# badge_0_1.net
KiCad netlist of a schematic drawn in EAGLE
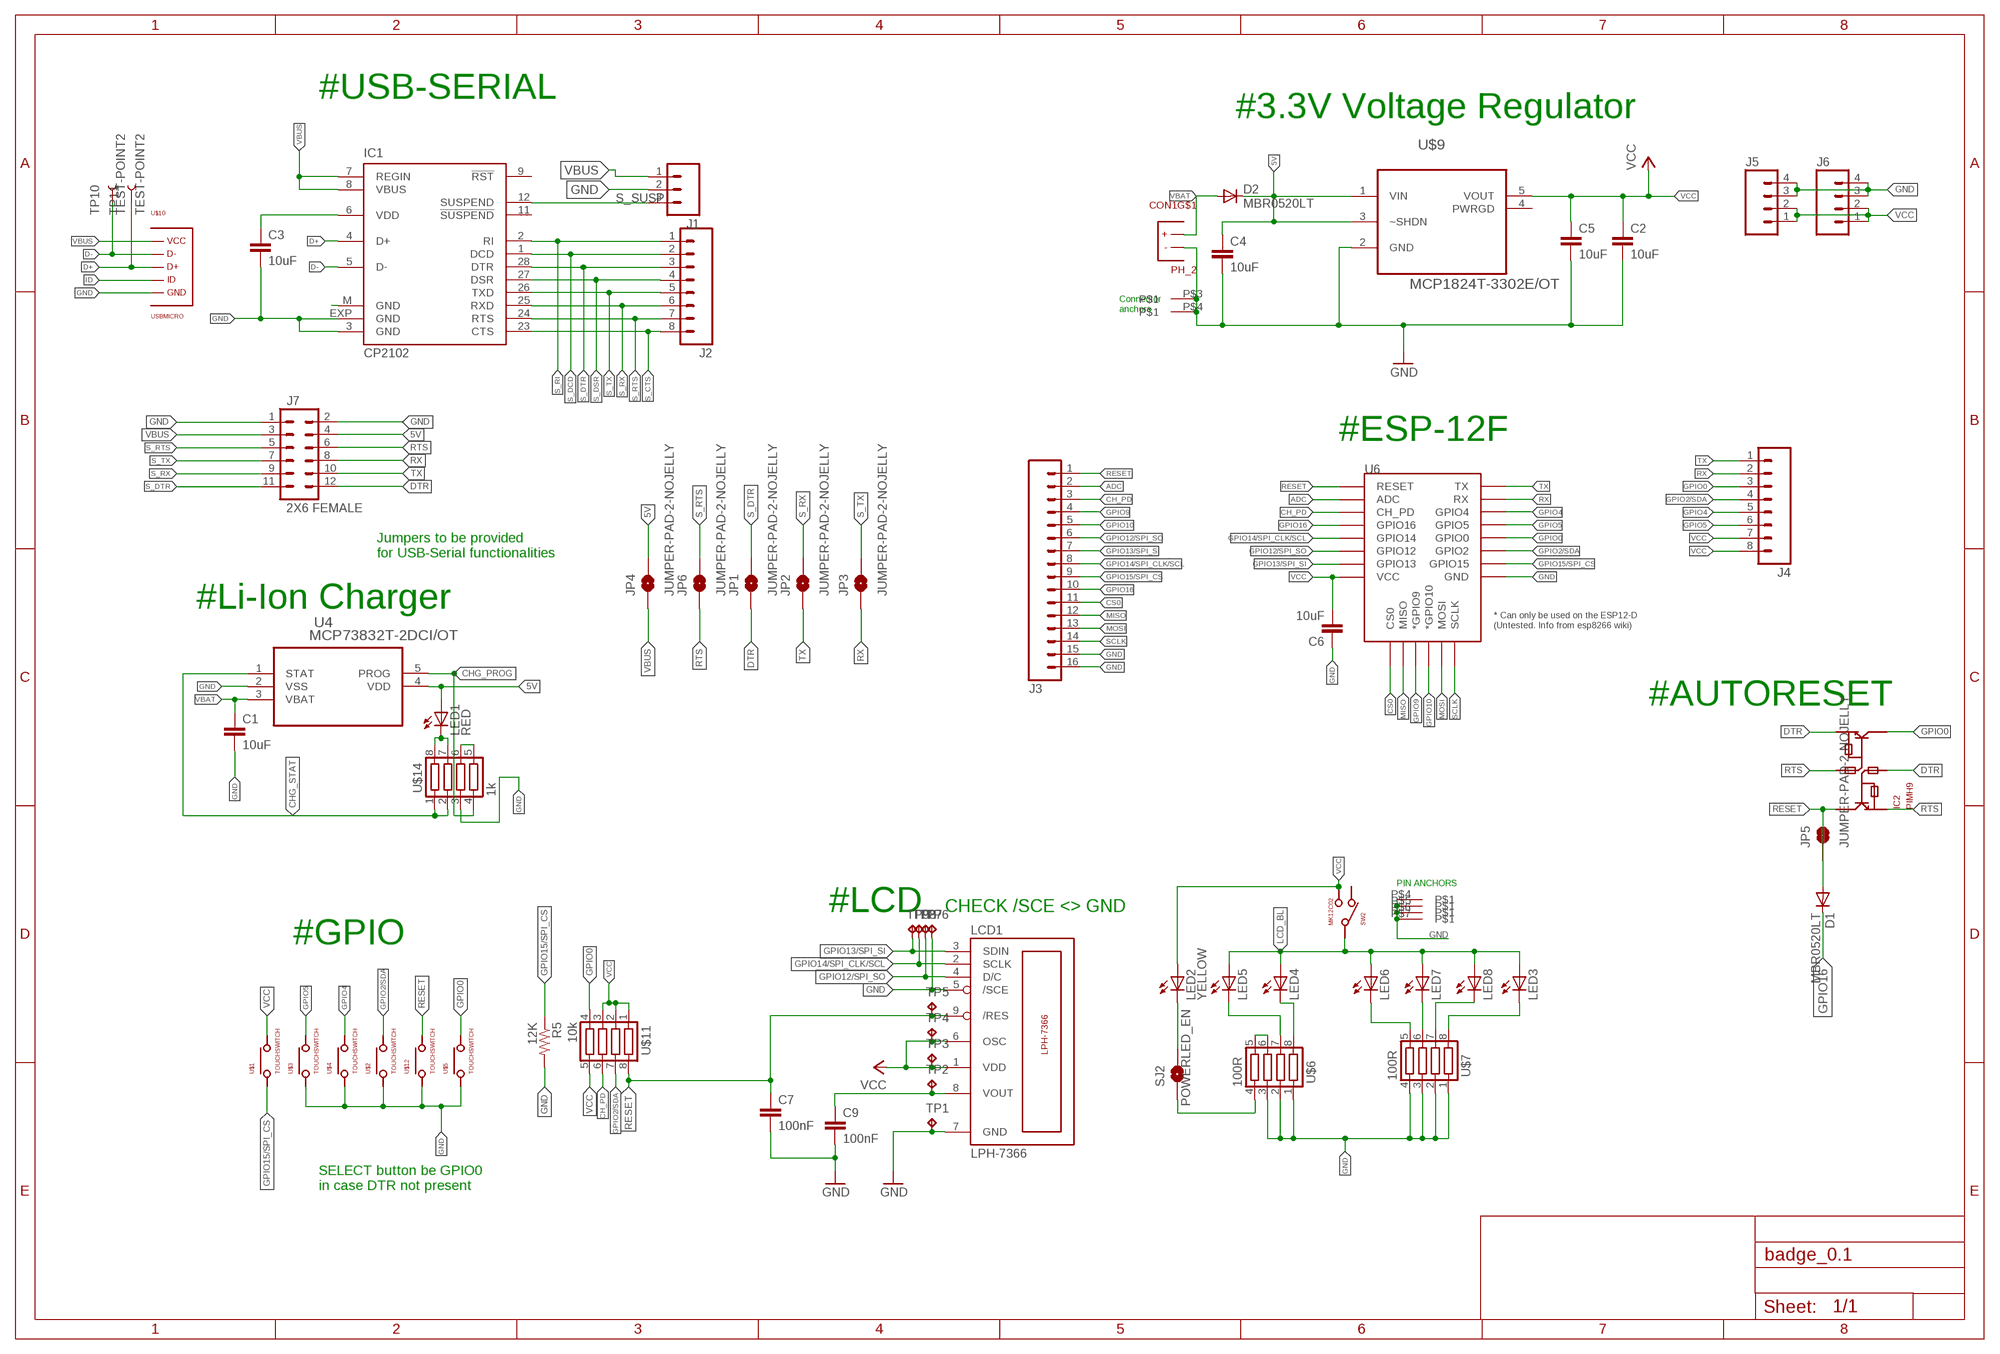
[diagram p0: schematic, sheet 1]

(export (version "E")
  (design (tool "Eeschema 10.0.6"))
  (components
    (comp (ref "C1")
      (value "10uF")
      (footprint "eagle-import:0805-CAP")
      (libsource (lib "eagle-import") (part "1UF-25V-10%(0805){dblquote}"))
    )
    (comp (ref "C2")
      (value "10uF")
      (footprint "eagle-import:0805-CAP")
      (libsource (lib "eagle-import") (part "1UF-25V-10%(0805){dblquote}"))
    )
    (comp (ref "C3")
      (value "10uF")
      (footprint "eagle-import:0805-CAP")
      (libsource (lib "eagle-import") (part "1UF-25V-10%(0805){dblquote}"))
    )
    (comp (ref "C4")
      (value "10uF")
      (footprint "eagle-import:0805-CAP")
      (libsource (lib "eagle-import") (part "1UF-25V-10%(0805){dblquote}"))
    )
    (comp (ref "C5")
      (value "10uF")
      (footprint "eagle-import:0805-CAP")
      (libsource (lib "eagle-import") (part "1UF-25V-10%(0805){dblquote}"))
    )
    (comp (ref "C6")
      (value "10uF")
      (footprint "eagle-import:0805-CAP")
      (libsource (lib "eagle-import") (part "1UF-25V-10%(0805){dblquote}"))
    )
    (comp (ref "C7")
      (value "100nF")
      (footprint "eagle-import:0805-CAP")
      (libsource (lib "eagle-import") (part "1UF-25V-10%(0805){dblquote}"))
    )
    (comp (ref "C9")
      (value "100nF")
      (footprint "eagle-import:0805-CAP")
      (libsource (lib "eagle-import") (part "1UF-25V-10%(0805){dblquote}"))
    )
    (comp (ref "CON1")
      (value "PH_2")
      (footprint "eagle-import:PH_2")
      (libsource (lib "eagle-import") (part "PH_2"))
    )
    (comp (ref "D1")
      (value "MBR0520LT")
      (footprint "eagle-import:SOD123")
      (libsource (lib "eagle-import") (part "MBR0520LT"))
    )
    (comp (ref "D2")
      (value "MBR0520LT")
      (footprint "eagle-import:SOD123")
      (libsource (lib "eagle-import") (part "MBR0520LT"))
    )
    (comp (ref "IC1")
      (value "CP2102")
      (footprint "eagle-import:MLP28")
      (fields (field (name "MF") "FARNELL") (field (name "MPN") "CP2102-GM"))
      (libsource (lib "eagle-import") (part "CP2102"))
    )
    (comp (ref "IC2")
      (value "PIMH9")
      (footprint "eagle-import:SOT457")
      (libsource (lib "eagle-import") (part "PIMH9"))
    )
    (comp (ref "J1")
      (value "M03PTH")
      (footprint "eagle-import:1X03")
      (libsource (lib "eagle-import") (part "M03PTH"))
    )
    (comp (ref "J2")
      (value "M08SILK_FEMALE_PTH")
      (footprint "eagle-import:1X08")
      (libsource (lib "eagle-import") (part "M08SILK_FEMALE_PTH"))
    )
    (comp (ref "J3")
      (value "M16PTH")
      (footprint "eagle-import:1X16")
      (libsource (lib "eagle-import") (part "M16PTH"))
    )
    (comp (ref "J4")
      (value "M08")
      (footprint "eagle-import:1X08_ROUND")
      (libsource (lib "eagle-import") (part "M08"))
    )
    (comp (ref "J5")
      (value "M04PTH")
      (footprint "eagle-import:1X04")
      (libsource (lib "eagle-import") (part "M04PTH"))
    )
    (comp (ref "J6")
      (value "M04PTH")
      (footprint "eagle-import:1X04")
      (libsource (lib "eagle-import") (part "M04PTH"))
    )
    (comp (ref "J7")
      (value "2X6 FEMALE")
      (footprint "eagle-import:2X6")
      (libsource (lib "eagle-import") (part "M06X2PTH_FEMALE"))
    )
    (comp (ref "JP1")
      (value "JUMPER-PAD-2-NOJELLY")
      (footprint "eagle-import:JELLYPAD-JUMPER-2-NO_NO_SILK")
      (libsource (lib "eagle-import") (part "JUMPER-PAD-2-NOJELLY"))
    )
    (comp (ref "JP2")
      (value "JUMPER-PAD-2-NOJELLY")
      (footprint "eagle-import:JELLYPAD-JUMPER-2-NO_NO_SILK")
      (libsource (lib "eagle-import") (part "JUMPER-PAD-2-NOJELLY"))
    )
    (comp (ref "JP3")
      (value "JUMPER-PAD-2-NOJELLY")
      (footprint "eagle-import:JELLYPAD-JUMPER-2-NO_NO_SILK")
      (libsource (lib "eagle-import") (part "JUMPER-PAD-2-NOJELLY"))
    )
    (comp (ref "JP4")
      (value "JUMPER-PAD-2-NOJELLY")
      (footprint "eagle-import:JELLYPAD-JUMPER-2-NO_NO_SILK")
      (libsource (lib "eagle-import") (part "JUMPER-PAD-2-NOJELLY"))
    )
    (comp (ref "JP5")
      (value "JUMPER-PAD-2-NOJELLY")
      (footprint "eagle-import:JELLYPAD-JUMPER-2-NO_NO_SILK")
      (libsource (lib "eagle-import") (part "JUMPER-PAD-2-NOJELLY"))
    )
    (comp (ref "JP6")
      (value "JUMPER-PAD-2-NOJELLY")
      (footprint "eagle-import:JELLYPAD-JUMPER-2-NO_NO_SILK")
      (libsource (lib "eagle-import") (part "JUMPER-PAD-2-NOJELLY"))
    )
    (comp (ref "LCD1")
      (value "LPH-7366")
      (footprint "eagle-import:LPH-7366")
      (libsource (lib "eagle-import") (part "LPH-7366"))
    )
    (comp (ref "LED1")
      (value "RED")
      (footprint "eagle-import:SML0805")
      (libsource (lib "eagle-import") (part "LEDSML0805"))
    )
    (comp (ref "LED2")
      (value "YELLOW")
      (footprint "eagle-import:SML0805")
      (libsource (lib "eagle-import") (part "LEDSML0805"))
    )
    (comp (ref "LED3")
      (value "LEDSML0805")
      (footprint "eagle-import:SML0805")
      (libsource (lib "eagle-import") (part "LEDSML0805"))
    )
    (comp (ref "LED4")
      (value "LEDSML0805")
      (footprint "eagle-import:SML0805")
      (libsource (lib "eagle-import") (part "LEDSML0805"))
    )
    (comp (ref "LED5")
      (value "LEDSML0805")
      (footprint "eagle-import:SML0805")
      (libsource (lib "eagle-import") (part "LEDSML0805"))
    )
    (comp (ref "LED6")
      (value "LEDSML0805")
      (footprint "eagle-import:SML0805")
      (libsource (lib "eagle-import") (part "LEDSML0805"))
    )
    (comp (ref "LED7")
      (value "LEDSML0805")
      (footprint "eagle-import:SML0805")
      (libsource (lib "eagle-import") (part "LEDSML0805"))
    )
    (comp (ref "LED8")
      (value "LEDSML0805")
      (footprint "eagle-import:SML0805")
      (libsource (lib "eagle-import") (part "LEDSML0805"))
    )
    (comp (ref "R5")
      (value "12K")
      (footprint "eagle-import:0805")
      (libsource (lib "eagle-import") (part "RESISTOR0805-RES"))
    )
    (comp (ref "SJ2")
      (value "POWERLED_EN")
      (footprint "eagle-import:SJ_2S-TRACE")
      (libsource (lib "eagle-import") (part "SOLDERJUMPERTRACE"))
    )
    (comp (ref "SW2")
      (value "MK12C02")
      (footprint "eagle-import:MK12C02")
      (libsource (lib "eagle-import") (part "MK12C02"))
    )
    (comp (ref "TP1")
      (value "TPB1,27")
      (footprint "eagle-import:B1,27")
      (libsource (lib "eagle-import") (part "TPB1,27"))
    )
    (comp (ref "TP2")
      (value "TPB1,27")
      (footprint "eagle-import:B1,27")
      (libsource (lib "eagle-import") (part "TPB1,27"))
    )
    (comp (ref "TP3")
      (value "TPB1,27")
      (footprint "eagle-import:B1,27")
      (libsource (lib "eagle-import") (part "TPB1,27"))
    )
    (comp (ref "TP4")
      (value "TPB1,27")
      (footprint "eagle-import:B1,27")
      (libsource (lib "eagle-import") (part "TPB1,27"))
    )
    (comp (ref "TP5")
      (value "TPB1,27")
      (footprint "eagle-import:B1,27")
      (libsource (lib "eagle-import") (part "TPB1,27"))
    )
    (comp (ref "TP6")
      (value "TPB1,27")
      (footprint "eagle-import:B1,27")
      (libsource (lib "eagle-import") (part "TPB1,27"))
    )
    (comp (ref "TP7")
      (value "TPB1,27")
      (footprint "eagle-import:B1,27")
      (libsource (lib "eagle-import") (part "TPB1,27"))
    )
    (comp (ref "TP8")
      (value "TPB1,27")
      (footprint "eagle-import:B1,27")
      (libsource (lib "eagle-import") (part "TPB1,27"))
    )
    (comp (ref "TP9")
      (value "TPB1,27")
      (footprint "eagle-import:B1,27")
      (libsource (lib "eagle-import") (part "TPB1,27"))
    )
    (comp (ref "TP10")
      (value "TEST-POINT2")
      (footprint "eagle-import:PAD.02X.02")
      (libsource (lib "eagle-import") (part "TEST-POINT2"))
    )
    (comp (ref "TP11")
      (value "TEST-POINT2")
      (footprint "eagle-import:PAD.02X.02")
      (libsource (lib "eagle-import") (part "TEST-POINT2"))
    )
    (comp (ref "U$1")
      (value "TOUCHSWITCH")
      (footprint "eagle-import:EVQQWN03W")
      (libsource (lib "eagle-import") (part "TOUCHSWITCH"))
    )
    (comp (ref "U$2")
      (value "TOUCHSWITCH")
      (footprint "eagle-import:EVQQWN03W")
      (libsource (lib "eagle-import") (part "TOUCHSWITCH"))
    )
    (comp (ref "U$3")
      (value "TOUCHSWITCH")
      (footprint "eagle-import:EVQQWN03W")
      (libsource (lib "eagle-import") (part "TOUCHSWITCH"))
    )
    (comp (ref "U$4")
      (value "TOUCHSWITCH")
      (footprint "eagle-import:EVQQWN03W")
      (libsource (lib "eagle-import") (part "TOUCHSWITCH"))
    )
    (comp (ref "U$5")
      (value "TOUCHSWITCH")
      (footprint "eagle-import:EVQQWN03W")
      (libsource (lib "eagle-import") (part "TOUCHSWITCH"))
    )
    (comp (ref "U$6")
      (value "100R")
      (footprint "eagle-import:YC164")
      (libsource (lib "eagle-import") (part "RES_ARR"))
    )
    (comp (ref "U$7")
      (value "100R")
      (footprint "eagle-import:YC164")
      (libsource (lib "eagle-import") (part "RES_ARR"))
    )
    (comp (ref "U$9")
      (value "MCP1824T-3302E/OT")
      (footprint "eagle-import:SOT95P270X145-5N")
      (libsource (lib "eagle-import") (part "MCP1824T-3302E/OT"))
    )
    (comp (ref "U$10")
      (value "USBMICRO")
      (footprint "eagle-import:USBMICRO")
      (libsource (lib "eagle-import") (part "USBMICRO"))
    )
    (comp (ref "U$11")
      (value "10k")
      (footprint "eagle-import:YC164")
      (libsource (lib "eagle-import") (part "RES_ARR"))
    )
    (comp (ref "U$12")
      (value "TOUCHSWITCH")
      (footprint "eagle-import:EVQQWN03W")
      (libsource (lib "eagle-import") (part "TOUCHSWITCH"))
    )
    (comp (ref "U$14")
      (value "1k")
      (footprint "eagle-import:YC164")
      (libsource (lib "eagle-import") (part "RES_ARR"))
    )
    (comp (ref "U4")
      (value "MCP73832T-2DCI/OT")
      (footprint "eagle-import:SOT95P300X145-5N")
      (libsource (lib "eagle-import") (part "MCP73832T-2DCI/OT"))
    )
    (comp (ref "U6")
      (value "ESP12ESMD")
      (footprint "eagle-import:ESP12E-SMD")
      (libsource (lib "eagle-import") (part "ESP12ESMD"))
    )
  )
  (nets
    (net (code "1") (name "/S_SUSP") (class "Default")
      (node (ref "IC1") (pin "12") (pinfunction "SUSPEND_12") (pintype "output"))
      (node (ref "J1") (pin "3") (pinfunction "3_3") (pintype "passive"))
    )
    (net (code "2") (name "5V") (class "Default")
      (node (ref "C4") (pin "1") (pinfunction "1_1") (pintype "passive"))
      (node (ref "D2") (pin "C") (pinfunction "C_C") (pintype "passive"))
      (node (ref "J7") (pin "4") (pinfunction "4_4") (pintype "passive"))
      (node (ref "JP4") (pin "2") (pinfunction "2_2") (pintype "passive"))
      (node (ref "LED1") (pin "A") (pinfunction "A_A") (pintype "passive"))
      (node (ref "U$9") (pin "1") (pinfunction "VIN_1") (pintype "input"))
      (node (ref "U$9") (pin "3") (pinfunction "~{SHDN}_3") (pintype "input"))
      (node (ref "U4") (pin "4") (pinfunction "VDD_4") (pintype "power_in"))
    )
    (net (code "3") (name "ADC") (class "Default")
      (node (ref "J3") (pin "2") (pinfunction "2_2") (pintype "passive"))
      (node (ref "U6") (pin "ADC") (pinfunction "ADC_ADC") (pintype "bidirectional"))
    )
    (net (code "4") (name "CHG_PROG") (class "Default")
      (node (ref "U$14") (pin "4") (pinfunction "4_4") (pintype "passive"))
      (node (ref "U4") (pin "5") (pinfunction "PROG_5") (pintype "input"))
    )
    (net (code "5") (name "CHG_STAT") (class "Default")
      (node (ref "U$14") (pin "1") (pinfunction "1_1") (pintype "passive"))
      (node (ref "U$14") (pin "2") (pinfunction "2_2") (pintype "passive"))
      (node (ref "U4") (pin "1") (pinfunction "STAT_1") (pintype "input"))
    )
    (net (code "6") (name "CH_PD") (class "Default")
      (node (ref "J3") (pin "3") (pinfunction "3_3") (pintype "passive"))
      (node (ref "U$11") (pin "6") (pinfunction "6_6") (pintype "passive"))
      (node (ref "U6") (pin "CH_PD") (pinfunction "CH_PD_CH_PD") (pintype "bidirectional"))
    )
    (net (code "7") (name "CS0") (class "Default")
      (node (ref "J3") (pin "11") (pinfunction "11_11") (pintype "passive"))
      (node (ref "U6") (pin "CS0") (pinfunction "CS0_CS0") (pintype "bidirectional"))
    )
    (net (code "8") (name "D+") (class "Default")
      (node (ref "IC1") (pin "4") (pinfunction "D+_4") (pintype "bidirectional"))
      (node (ref "TP11") (pin "P$1") (pinfunction "1_P$1") (pintype "bidirectional"))
      (node (ref "U$10") (pin "P$D+") (pinfunction "P$D+_P$D+") (pintype "bidirectional"))
    )
    (net (code "9") (name "D-") (class "Default")
      (node (ref "IC1") (pin "5") (pinfunction "D-_5") (pintype "bidirectional"))
      (node (ref "TP10") (pin "P$1") (pinfunction "1_P$1") (pintype "bidirectional"))
      (node (ref "U$10") (pin "P$D-") (pinfunction "P$D-_P$D-") (pintype "bidirectional"))
    )
    (net (code "10") (name "DTR") (class "Default")
      (node (ref "IC2") (pin "P$2") (pinfunction "P$2_P$2") (pintype "bidirectional"))
      (node (ref "IC2") (pin "P$4") (pinfunction "P$4_P$4") (pintype "bidirectional"))
      (node (ref "J7") (pin "12") (pinfunction "12_12") (pintype "passive"))
      (node (ref "JP1") (pin "1") (pinfunction "1_1") (pintype "passive"))
    )
    (net (code "11") (name "GND") (class "Default")
      (node (ref "C1") (pin "2") (pinfunction "2_2") (pintype "passive"))
      (node (ref "C2") (pin "2") (pinfunction "2_2") (pintype "passive"))
      (node (ref "C3") (pin "2") (pinfunction "2_2") (pintype "passive"))
      (node (ref "C4") (pin "2") (pinfunction "2_2") (pintype "passive"))
      (node (ref "C5") (pin "2") (pinfunction "2_2") (pintype "passive"))
      (node (ref "C6") (pin "1") (pinfunction "1_1") (pintype "passive"))
      (node (ref "C7") (pin "2") (pinfunction "2_2") (pintype "passive"))
      (node (ref "C9") (pin "2") (pinfunction "2_2") (pintype "passive"))
      (node (ref "CON1") (pin "P$1") (pinfunction "P$2_P$1") (pintype "bidirectional"))
      (node (ref "CON1") (pin "P$3") (pinfunction "P$1_P$3") (pintype "bidirectional"))
      (node (ref "CON1") (pin "P$4") (pinfunction "P$1_P$4") (pintype "bidirectional"))
      (node (ref "IC1") (pin "3") (pinfunction "GND_3") (pintype "power_in"))
      (node (ref "IC1") (pin "EXP") (pinfunction "GND_EXP") (pintype "power_in"))
      (node (ref "J1") (pin "2") (pinfunction "2_2") (pintype "passive"))
      (node (ref "J3") (pin "15") (pinfunction "15_15") (pintype "passive"))
      (node (ref "J3") (pin "16") (pinfunction "16_16") (pintype "passive"))
      (node (ref "J5") (pin "3") (pinfunction "3_3") (pintype "passive"))
      (node (ref "J5") (pin "4") (pinfunction "4_4") (pintype "passive"))
      (node (ref "J6") (pin "3") (pinfunction "3_3") (pintype "passive"))
      (node (ref "J6") (pin "4") (pinfunction "4_4") (pintype "passive"))
      (node (ref "J7") (pin "1") (pinfunction "1_1") (pintype "passive"))
      (node (ref "J7") (pin "2") (pinfunction "2_2") (pintype "passive"))
      (node (ref "LCD1") (pin "5") (pinfunction "/SCE_5") (pintype "input"))
      (node (ref "LCD1") (pin "7") (pinfunction "GND_7") (pintype "power_in"))
      (node (ref "R5") (pin "2") (pinfunction "2_2") (pintype "passive"))
      (node (ref "SW2") (pin "P$4") (pinfunction "P$1_P$4") (pintype "bidirectional"))
      (node (ref "SW2") (pin "P$5") (pinfunction "P$1_P$5") (pintype "bidirectional"))
      (node (ref "SW2") (pin "P$6") (pinfunction "P$1_P$6") (pintype "bidirectional"))
      (node (ref "SW2") (pin "P$7") (pinfunction "P$1_P$7") (pintype "bidirectional"))
      (node (ref "TP1") (pin "TP") (pinfunction "TP_TP") (pintype "input"))
      (node (ref "TP6") (pin "TP") (pinfunction "TP_TP") (pintype "input"))
      (node (ref "U$10") (pin "P$GND") (pinfunction "P$GND_P$GND") (pintype "bidirectional"))
      (node (ref "U$12") (pin "P$1") (pinfunction "P$1_P$1") (pintype "bidirectional"))
      (node (ref "U$12") (pin "P$4") (pinfunction "P$1_P$4") (pintype "bidirectional"))
      (node (ref "U$14") (pin "3") (pinfunction "3_3") (pintype "passive"))
      (node (ref "U$2") (pin "P$1") (pinfunction "P$1_P$1") (pintype "bidirectional"))
      (node (ref "U$2") (pin "P$4") (pinfunction "P$1_P$4") (pintype "bidirectional"))
      (node (ref "U$3") (pin "P$1") (pinfunction "P$1_P$1") (pintype "bidirectional"))
      (node (ref "U$3") (pin "P$4") (pinfunction "P$1_P$4") (pintype "bidirectional"))
      (node (ref "U$4") (pin "P$1") (pinfunction "P$1_P$1") (pintype "bidirectional"))
      (node (ref "U$4") (pin "P$4") (pinfunction "P$1_P$4") (pintype "bidirectional"))
      (node (ref "U$5") (pin "P$1") (pinfunction "P$1_P$1") (pintype "bidirectional"))
      (node (ref "U$5") (pin "P$4") (pinfunction "P$1_P$4") (pintype "bidirectional"))
      (node (ref "U$6") (pin "1") (pinfunction "1_1") (pintype "passive"))
      (node (ref "U$6") (pin "2") (pinfunction "2_2") (pintype "passive"))
      (node (ref "U$6") (pin "3") (pinfunction "3_3") (pintype "passive"))
      (node (ref "U$7") (pin "1") (pinfunction "1_1") (pintype "passive"))
      (node (ref "U$7") (pin "2") (pinfunction "2_2") (pintype "passive"))
      (node (ref "U$7") (pin "3") (pinfunction "3_3") (pintype "passive"))
      (node (ref "U$7") (pin "4") (pinfunction "4_4") (pintype "passive"))
      (node (ref "U$9") (pin "2") (pinfunction "GND_2") (pintype "passive"))
      (node (ref "U4") (pin "2") (pinfunction "VSS_2") (pintype "passive"))
      (node (ref "U6") (pin "GND") (pinfunction "GND_GND") (pintype "bidirectional"))
    )
    (net (code "12") (name "GPIO0") (class "Default")
      (node (ref "IC2") (pin "P$3") (pinfunction "P$3_P$3") (pintype "bidirectional"))
      (node (ref "J4") (pin "3") (pinfunction "3_3") (pintype "passive"))
      (node (ref "U$11") (pin "4") (pinfunction "4_4") (pintype "passive"))
      (node (ref "U$5") (pin "P$2") (pinfunction "P$2_P$2") (pintype "bidirectional"))
      (node (ref "U$5") (pin "P$3") (pinfunction "P$2_P$3") (pintype "bidirectional"))
      (node (ref "U6") (pin "GPIO0") (pinfunction "GPIO0_GPIO0") (pintype "bidirectional"))
    )
    (net (code "13") (name "GPIO2{slash}SDA") (class "Default")
      (node (ref "J4") (pin "4") (pinfunction "4_4") (pintype "passive"))
      (node (ref "U$11") (pin "7") (pinfunction "7_7") (pintype "passive"))
      (node (ref "U$2") (pin "P$2") (pinfunction "P$2_P$2") (pintype "bidirectional"))
      (node (ref "U$2") (pin "P$3") (pinfunction "P$2_P$3") (pintype "bidirectional"))
      (node (ref "U6") (pin "GPIO2") (pinfunction "GPIO2_GPIO2") (pintype "bidirectional"))
    )
    (net (code "14") (name "GPIO4") (class "Default")
      (node (ref "J4") (pin "5") (pinfunction "5_5") (pintype "passive"))
      (node (ref "U$4") (pin "P$2") (pinfunction "P$2_P$2") (pintype "bidirectional"))
      (node (ref "U$4") (pin "P$3") (pinfunction "P$2_P$3") (pintype "bidirectional"))
      (node (ref "U6") (pin "GPIO4") (pinfunction "GPIO4_GPIO4") (pintype "bidirectional"))
    )
    (net (code "15") (name "GPIO5") (class "Default")
      (node (ref "J4") (pin "6") (pinfunction "6_6") (pintype "passive"))
      (node (ref "U$3") (pin "P$2") (pinfunction "P$2_P$2") (pintype "bidirectional"))
      (node (ref "U$3") (pin "P$3") (pinfunction "P$2_P$3") (pintype "bidirectional"))
      (node (ref "U6") (pin "GPIO5") (pinfunction "GPIO5_GPIO5") (pintype "bidirectional"))
    )
    (net (code "16") (name "GPIO9") (class "Default")
      (node (ref "J3") (pin "4") (pinfunction "4_4") (pintype "passive"))
      (node (ref "U6") (pin "GPIO9") (pinfunction "*GPIO9_GPIO9") (pintype "bidirectional"))
    )
    (net (code "17") (name "GPIO10") (class "Default")
      (node (ref "J3") (pin "5") (pinfunction "5_5") (pintype "passive"))
      (node (ref "U6") (pin "GPIO10") (pinfunction "*GPIO10_GPIO10") (pintype "bidirectional"))
    )
    (net (code "18") (name "GPIO12{slash}SPI_SO") (class "Default")
      (node (ref "J3") (pin "6") (pinfunction "6_6") (pintype "passive"))
      (node (ref "LCD1") (pin "4") (pinfunction "D/C_4") (pintype "input"))
      (node (ref "TP7") (pin "TP") (pinfunction "TP_TP") (pintype "input"))
      (node (ref "U6") (pin "GPIO12") (pinfunction "GPIO12_GPIO12") (pintype "bidirectional"))
    )
    (net (code "19") (name "GPIO13{slash}SPI_SI") (class "Default")
      (node (ref "J3") (pin "7") (pinfunction "7_7") (pintype "passive"))
      (node (ref "LCD1") (pin "3") (pinfunction "SDIN_3") (pintype "input"))
      (node (ref "TP9") (pin "TP") (pinfunction "TP_TP") (pintype "input"))
      (node (ref "U6") (pin "GPIO13") (pinfunction "GPIO13_GPIO13") (pintype "bidirectional"))
    )
    (net (code "20") (name "GPIO14{slash}SPI_CLK{slash}SCL") (class "Default")
      (node (ref "J3") (pin "8") (pinfunction "8_8") (pintype "passive"))
      (node (ref "LCD1") (pin "2") (pinfunction "SCLK_2") (pintype "input"))
      (node (ref "TP8") (pin "TP") (pinfunction "TP_TP") (pintype "input"))
      (node (ref "U6") (pin "GPIO14") (pinfunction "GPIO14_GPIO14") (pintype "bidirectional"))
    )
    (net (code "21") (name "GPIO15{slash}SPI_CS") (class "Default")
      (node (ref "J3") (pin "9") (pinfunction "9_9") (pintype "passive"))
      (node (ref "R5") (pin "1") (pinfunction "1_1") (pintype "passive"))
      (node (ref "U$1") (pin "P$1") (pinfunction "P$1_P$1") (pintype "bidirectional"))
      (node (ref "U$1") (pin "P$4") (pinfunction "P$1_P$4") (pintype "bidirectional"))
      (node (ref "U6") (pin "GPIO15") (pinfunction "GPIO15_GPIO15") (pintype "bidirectional"))
    )
    (net (code "22") (name "GPIO16") (class "Default")
      (node (ref "D1") (pin "C") (pinfunction "C_C") (pintype "passive"))
      (node (ref "J3") (pin "10") (pinfunction "10_10") (pintype "passive"))
      (node (ref "U6") (pin "GPIO16") (pinfunction "GPIO16_GPIO16") (pintype "bidirectional"))
    )
    (net (code "23") (name "ID") (class "Default")
      (node (ref "U$10") (pin "P$ID") (pinfunction "P$ID_P$ID") (pintype "bidirectional"))
    )
    (net (code "24") (name "LCD_BL") (class "Default")
      (node (ref "LED3") (pin "A") (pinfunction "A_A") (pintype "passive"))
      (node (ref "LED4") (pin "A") (pinfunction "A_A") (pintype "passive"))
      (node (ref "LED5") (pin "A") (pinfunction "A_A") (pintype "passive"))
      (node (ref "LED6") (pin "A") (pinfunction "A_A") (pintype "passive"))
      (node (ref "LED7") (pin "A") (pinfunction "A_A") (pintype "passive"))
      (node (ref "LED8") (pin "A") (pinfunction "A_A") (pintype "passive"))
      (node (ref "SW2") (pin "P$2") (pinfunction "P$1_P$2") (pintype "bidirectional"))
    )
    (net (code "25") (name "MISO") (class "Default")
      (node (ref "J3") (pin "12") (pinfunction "12_12") (pintype "passive"))
      (node (ref "U6") (pin "MISO") (pinfunction "MISO_MISO") (pintype "bidirectional"))
    )
    (net (code "26") (name "MOSI") (class "Default")
      (node (ref "J3") (pin "13") (pinfunction "13_13") (pintype "passive"))
      (node (ref "U6") (pin "MOSI") (pinfunction "MOSI_MOSI") (pintype "bidirectional"))
    )
    (net (code "27") (name "Net-(IC1-VDD)") (class "Default")
      (node (ref "C3") (pin "1") (pinfunction "1_1") (pintype "passive"))
      (node (ref "IC1") (pin "6") (pinfunction "VDD_6") (pintype "power_in"))
    )
    (net (code "28") (name "Net-(LCD1-VOUT)") (class "Default")
      (node (ref "C9") (pin "1") (pinfunction "1_1") (pintype "passive"))
      (node (ref "LCD1") (pin "8") (pinfunction "VOUT_8") (pintype "passive"))
      (node (ref "TP2") (pin "TP") (pinfunction "TP_TP") (pintype "input"))
    )
    (net (code "29") (name "Net-(LED1-PadC)") (class "Default")
      (node (ref "LED1") (pin "C") (pinfunction "C_C") (pintype "passive"))
      (node (ref "U$14") (pin "7") (pinfunction "7_7") (pintype "passive"))
      (node (ref "U$14") (pin "8") (pinfunction "8_8") (pintype "passive"))
    )
    (net (code "30") (name "Net-(LED2-PadC)") (class "Default")
      (node (ref "LED2") (pin "C") (pinfunction "C_C") (pintype "passive"))
      (node (ref "SJ2") (pin "2") (pinfunction "2_2") (pintype "passive"))
    )
    (net (code "31") (name "Net-(LED3-PadC)") (class "Default")
      (node (ref "LED3") (pin "C") (pinfunction "C_C") (pintype "passive"))
      (node (ref "U$7") (pin "8") (pinfunction "8_8") (pintype "passive"))
    )
    (net (code "32") (name "Net-(LED4-PadC)") (class "Default")
      (node (ref "LED4") (pin "C") (pinfunction "C_C") (pintype "passive"))
      (node (ref "U$6") (pin "8") (pinfunction "8_8") (pintype "passive"))
    )
    (net (code "33") (name "Net-(LED5-PadC)") (class "Default")
      (node (ref "LED5") (pin "C") (pinfunction "C_C") (pintype "passive"))
      (node (ref "U$6") (pin "7") (pinfunction "7_7") (pintype "passive"))
    )
    (net (code "34") (name "Net-(LED6-PadC)") (class "Default")
      (node (ref "LED6") (pin "C") (pinfunction "C_C") (pintype "passive"))
      (node (ref "U$7") (pin "5") (pinfunction "5_5") (pintype "passive"))
    )
    (net (code "35") (name "Net-(LED7-PadC)") (class "Default")
      (node (ref "LED7") (pin "C") (pinfunction "C_C") (pintype "passive"))
      (node (ref "U$7") (pin "6") (pinfunction "6_6") (pintype "passive"))
    )
    (net (code "36") (name "Net-(LED8-PadC)") (class "Default")
      (node (ref "LED8") (pin "C") (pinfunction "C_C") (pintype "passive"))
      (node (ref "U$7") (pin "7") (pinfunction "7_7") (pintype "passive"))
    )
    (net (code "37") (name "Net-(SJ2-Pad1)") (class "Default")
      (node (ref "SJ2") (pin "1") (pinfunction "1_1") (pintype "passive"))
      (node (ref "U$6") (pin "4") (pinfunction "4_4") (pintype "passive"))
    )
    (net (code "38") (name "Net-(U$6-Pad5)") (class "Default")
      (node (ref "U$6") (pin "5") (pinfunction "5_5") (pintype "passive"))
      (node (ref "U$6") (pin "6") (pinfunction "6_6") (pintype "passive"))
    )
    (net (code "39") (name "Net-(U$14-Pad5)") (class "Default")
      (node (ref "U$14") (pin "5") (pinfunction "5_5") (pintype "passive"))
      (node (ref "U$14") (pin "6") (pinfunction "6_6") (pintype "passive"))
    )
    (net (code "40") (name "RESET") (class "Default")
      (node (ref "C7") (pin "1") (pinfunction "1_1") (pintype "passive"))
      (node (ref "D1") (pin "A") (pinfunction "A_A") (pintype "passive"))
      (node (ref "IC2") (pin "P$6") (pinfunction "P$6_P$6") (pintype "bidirectional"))
      (node (ref "J3") (pin "1") (pinfunction "1_1") (pintype "passive"))
      (node (ref "JP5") (pin "1") (pinfunction "1_1") (pintype "passive"))
      (node (ref "JP5") (pin "2") (pinfunction "2_2") (pintype "passive"))
      (node (ref "LCD1") (pin "9") (pinfunction "/RES_9") (pintype "input"))
      (node (ref "TP5") (pin "TP") (pinfunction "TP_TP") (pintype "input"))
      (node (ref "U$11") (pin "8") (pinfunction "8_8") (pintype "passive"))
      (node (ref "U$12") (pin "P$2") (pinfunction "P$2_P$2") (pintype "bidirectional"))
      (node (ref "U$12") (pin "P$3") (pinfunction "P$2_P$3") (pintype "bidirectional"))
      (node (ref "U6") (pin "RESET") (pinfunction "RESET_RESET") (pintype "bidirectional"))
    )
    (net (code "41") (name "RTS") (class "Default")
      (node (ref "IC2") (pin "P$1") (pinfunction "P$1_P$1") (pintype "bidirectional"))
      (node (ref "IC2") (pin "P$5") (pinfunction "P$5_P$5") (pintype "bidirectional"))
      (node (ref "J7") (pin "6") (pinfunction "6_6") (pintype "passive"))
      (node (ref "JP6") (pin "1") (pinfunction "1_1") (pintype "passive"))
    )
    (net (code "42") (name "RX") (class "Default")
      (node (ref "J4") (pin "2") (pinfunction "2_2") (pintype "passive"))
      (node (ref "J7") (pin "8") (pinfunction "8_8") (pintype "passive"))
      (node (ref "JP3") (pin "1") (pinfunction "1_1") (pintype "passive"))
      (node (ref "U6") (pin "RXD0") (pinfunction "RX_RXD0") (pintype "bidirectional"))
    )
    (net (code "43") (name "SCLK") (class "Default")
      (node (ref "J3") (pin "14") (pinfunction "14_14") (pintype "passive"))
      (node (ref "U6") (pin "SCLK") (pinfunction "SCLK_SCLK") (pintype "bidirectional"))
    )
    (net (code "44") (name "S_CTS") (class "Default")
      (node (ref "IC1") (pin "23") (pinfunction "CTS_23") (pintype "input"))
      (node (ref "J2") (pin "8") (pinfunction "8_8") (pintype "passive"))
    )
    (net (code "45") (name "S_DCD") (class "Default")
      (node (ref "IC1") (pin "1") (pinfunction "DCD_1") (pintype "input"))
      (node (ref "J2") (pin "2") (pinfunction "2_2") (pintype "passive"))
    )
    (net (code "46") (name "S_DSR") (class "Default")
      (node (ref "IC1") (pin "27") (pinfunction "DSR_27") (pintype "input"))
      (node (ref "J2") (pin "4") (pinfunction "4_4") (pintype "passive"))
    )
    (net (code "47") (name "S_DTR") (class "Default")
      (node (ref "IC1") (pin "28") (pinfunction "DTR_28") (pintype "output"))
      (node (ref "J2") (pin "3") (pinfunction "3_3") (pintype "passive"))
      (node (ref "J7") (pin "11") (pinfunction "11_11") (pintype "passive"))
      (node (ref "JP1") (pin "2") (pinfunction "2_2") (pintype "passive"))
    )
    (net (code "48") (name "S_RI") (class "Default")
      (node (ref "IC1") (pin "2") (pinfunction "RI_2") (pintype "input"))
      (node (ref "J2") (pin "1") (pinfunction "1_1") (pintype "passive"))
    )
    (net (code "49") (name "S_RTS") (class "Default")
      (node (ref "IC1") (pin "24") (pinfunction "RTS_24") (pintype "output"))
      (node (ref "J2") (pin "7") (pinfunction "7_7") (pintype "passive"))
      (node (ref "J7") (pin "5") (pinfunction "5_5") (pintype "passive"))
      (node (ref "JP6") (pin "2") (pinfunction "2_2") (pintype "passive"))
    )
    (net (code "50") (name "S_RX") (class "Default")
      (node (ref "IC1") (pin "25") (pinfunction "RXD_25") (pintype "input"))
      (node (ref "J2") (pin "6") (pinfunction "6_6") (pintype "passive"))
      (node (ref "J7") (pin "9") (pinfunction "9_9") (pintype "passive"))
      (node (ref "JP2") (pin "2") (pinfunction "2_2") (pintype "passive"))
    )
    (net (code "51") (name "S_TX") (class "Default")
      (node (ref "IC1") (pin "26") (pinfunction "TXD_26") (pintype "output"))
      (node (ref "J2") (pin "5") (pinfunction "5_5") (pintype "passive"))
      (node (ref "J7") (pin "7") (pinfunction "7_7") (pintype "passive"))
      (node (ref "JP3") (pin "2") (pinfunction "2_2") (pintype "passive"))
    )
    (net (code "52") (name "TX") (class "Default")
      (node (ref "J4") (pin "1") (pinfunction "1_1") (pintype "passive"))
      (node (ref "J7") (pin "10") (pinfunction "10_10") (pintype "passive"))
      (node (ref "JP2") (pin "1") (pinfunction "1_1") (pintype "passive"))
      (node (ref "U6") (pin "TXD0") (pinfunction "TX_TXD0") (pintype "bidirectional"))
    )
    (net (code "53") (name "VBAT") (class "Default")
      (node (ref "C1") (pin "1") (pinfunction "1_1") (pintype "passive"))
      (node (ref "CON1") (pin "P$2") (pinfunction "P$1_P$2") (pintype "bidirectional"))
      (node (ref "D2") (pin "A") (pinfunction "A_A") (pintype "passive"))
      (node (ref "U4") (pin "3") (pinfunction "VBAT_3") (pintype "input"))
    )
    (net (code "54") (name "VBUS") (class "Default")
      (node (ref "IC1") (pin "7") (pinfunction "REGIN_7") (pintype "passive"))
      (node (ref "IC1") (pin "8") (pinfunction "VBUS_8") (pintype "input"))
      (node (ref "J1") (pin "1") (pinfunction "1_1") (pintype "passive"))
      (node (ref "J7") (pin "3") (pinfunction "3_3") (pintype "passive"))
      (node (ref "JP4") (pin "1") (pinfunction "1_1") (pintype "passive"))
      (node (ref "U$10") (pin "P$VCC") (pinfunction "P$VCC_P$VCC") (pintype "bidirectional"))
    )
    (net (code "55") (name "VCC") (class "Default")
      (node (ref "C2") (pin "1") (pinfunction "1_1") (pintype "passive"))
      (node (ref "C5") (pin "1") (pinfunction "1_1") (pintype "passive"))
      (node (ref "C6") (pin "2") (pinfunction "2_2") (pintype "passive"))
      (node (ref "J4") (pin "7") (pinfunction "7_7") (pintype "passive"))
      (node (ref "J4") (pin "8") (pinfunction "8_8") (pintype "passive"))
      (node (ref "J5") (pin "1") (pinfunction "1_1") (pintype "passive"))
      (node (ref "J5") (pin "2") (pinfunction "2_2") (pintype "passive"))
      (node (ref "J6") (pin "1") (pinfunction "1_1") (pintype "passive"))
      (node (ref "J6") (pin "2") (pinfunction "2_2") (pintype "passive"))
      (node (ref "LCD1") (pin "1") (pinfunction "VDD_1") (pintype "power_in"))
      (node (ref "LCD1") (pin "6") (pinfunction "OSC_6") (pintype "passive"))
      (node (ref "LED2") (pin "A") (pinfunction "A_A") (pintype "passive"))
      (node (ref "SW2") (pin "P$3") (pinfunction "P$3_P$3") (pintype "bidirectional"))
      (node (ref "TP3") (pin "TP") (pinfunction "TP_TP") (pintype "input"))
      (node (ref "TP4") (pin "TP") (pinfunction "TP_TP") (pintype "input"))
      (node (ref "U$1") (pin "P$2") (pinfunction "P$2_P$2") (pintype "bidirectional"))
      (node (ref "U$1") (pin "P$3") (pinfunction "P$2_P$3") (pintype "bidirectional"))
      (node (ref "U$11") (pin "1") (pinfunction "1_1") (pintype "passive"))
      (node (ref "U$11") (pin "2") (pinfunction "2_2") (pintype "passive"))
      (node (ref "U$11") (pin "3") (pinfunction "3_3") (pintype "passive"))
      (node (ref "U$11") (pin "5") (pinfunction "5_5") (pintype "passive"))
      (node (ref "U$9") (pin "5") (pinfunction "VOUT_5") (pintype "output"))
      (node (ref "U6") (pin "VCC") (pinfunction "VCC_VCC") (pintype "bidirectional"))
    )
    (net (code "56") (name "unconnected-(IC1-GND-PadM)") (class "Default")
      (node (ref "IC1") (pin "M") (pinfunction "GND_M") (pintype "power_in"))
    )
    (net (code "57") (name "unconnected-(IC1-~{RST}-Pad9)") (class "Default")
      (node (ref "IC1") (pin "9") (pinfunction "~{RST}_9") (pintype "bidirectional"))
    )
    (net (code "58") (name "unconnected-(IC1-~{SUSPEND}-Pad11)") (class "Default")
      (node (ref "IC1") (pin "11") (pinfunction "~{SUSPEND}_11") (pintype "output"))
    )
    (net (code "59") (name "unconnected-(SW2A-P$2-PadP$1)") (class "Default")
      (node (ref "SW2") (pin "P$1") (pinfunction "P$2_P$1") (pintype "bidirectional"))
    )
    (net (code "60") (name "unconnected-(U$9-PWRGD-Pad4)") (class "Default")
      (node (ref "U$9") (pin "4") (pinfunction "PWRGD_4") (pintype "output"))
    )
  )
)
